# carcomputer_split3_top.net
KiCad netlist of a schematic drawn in EAGLE
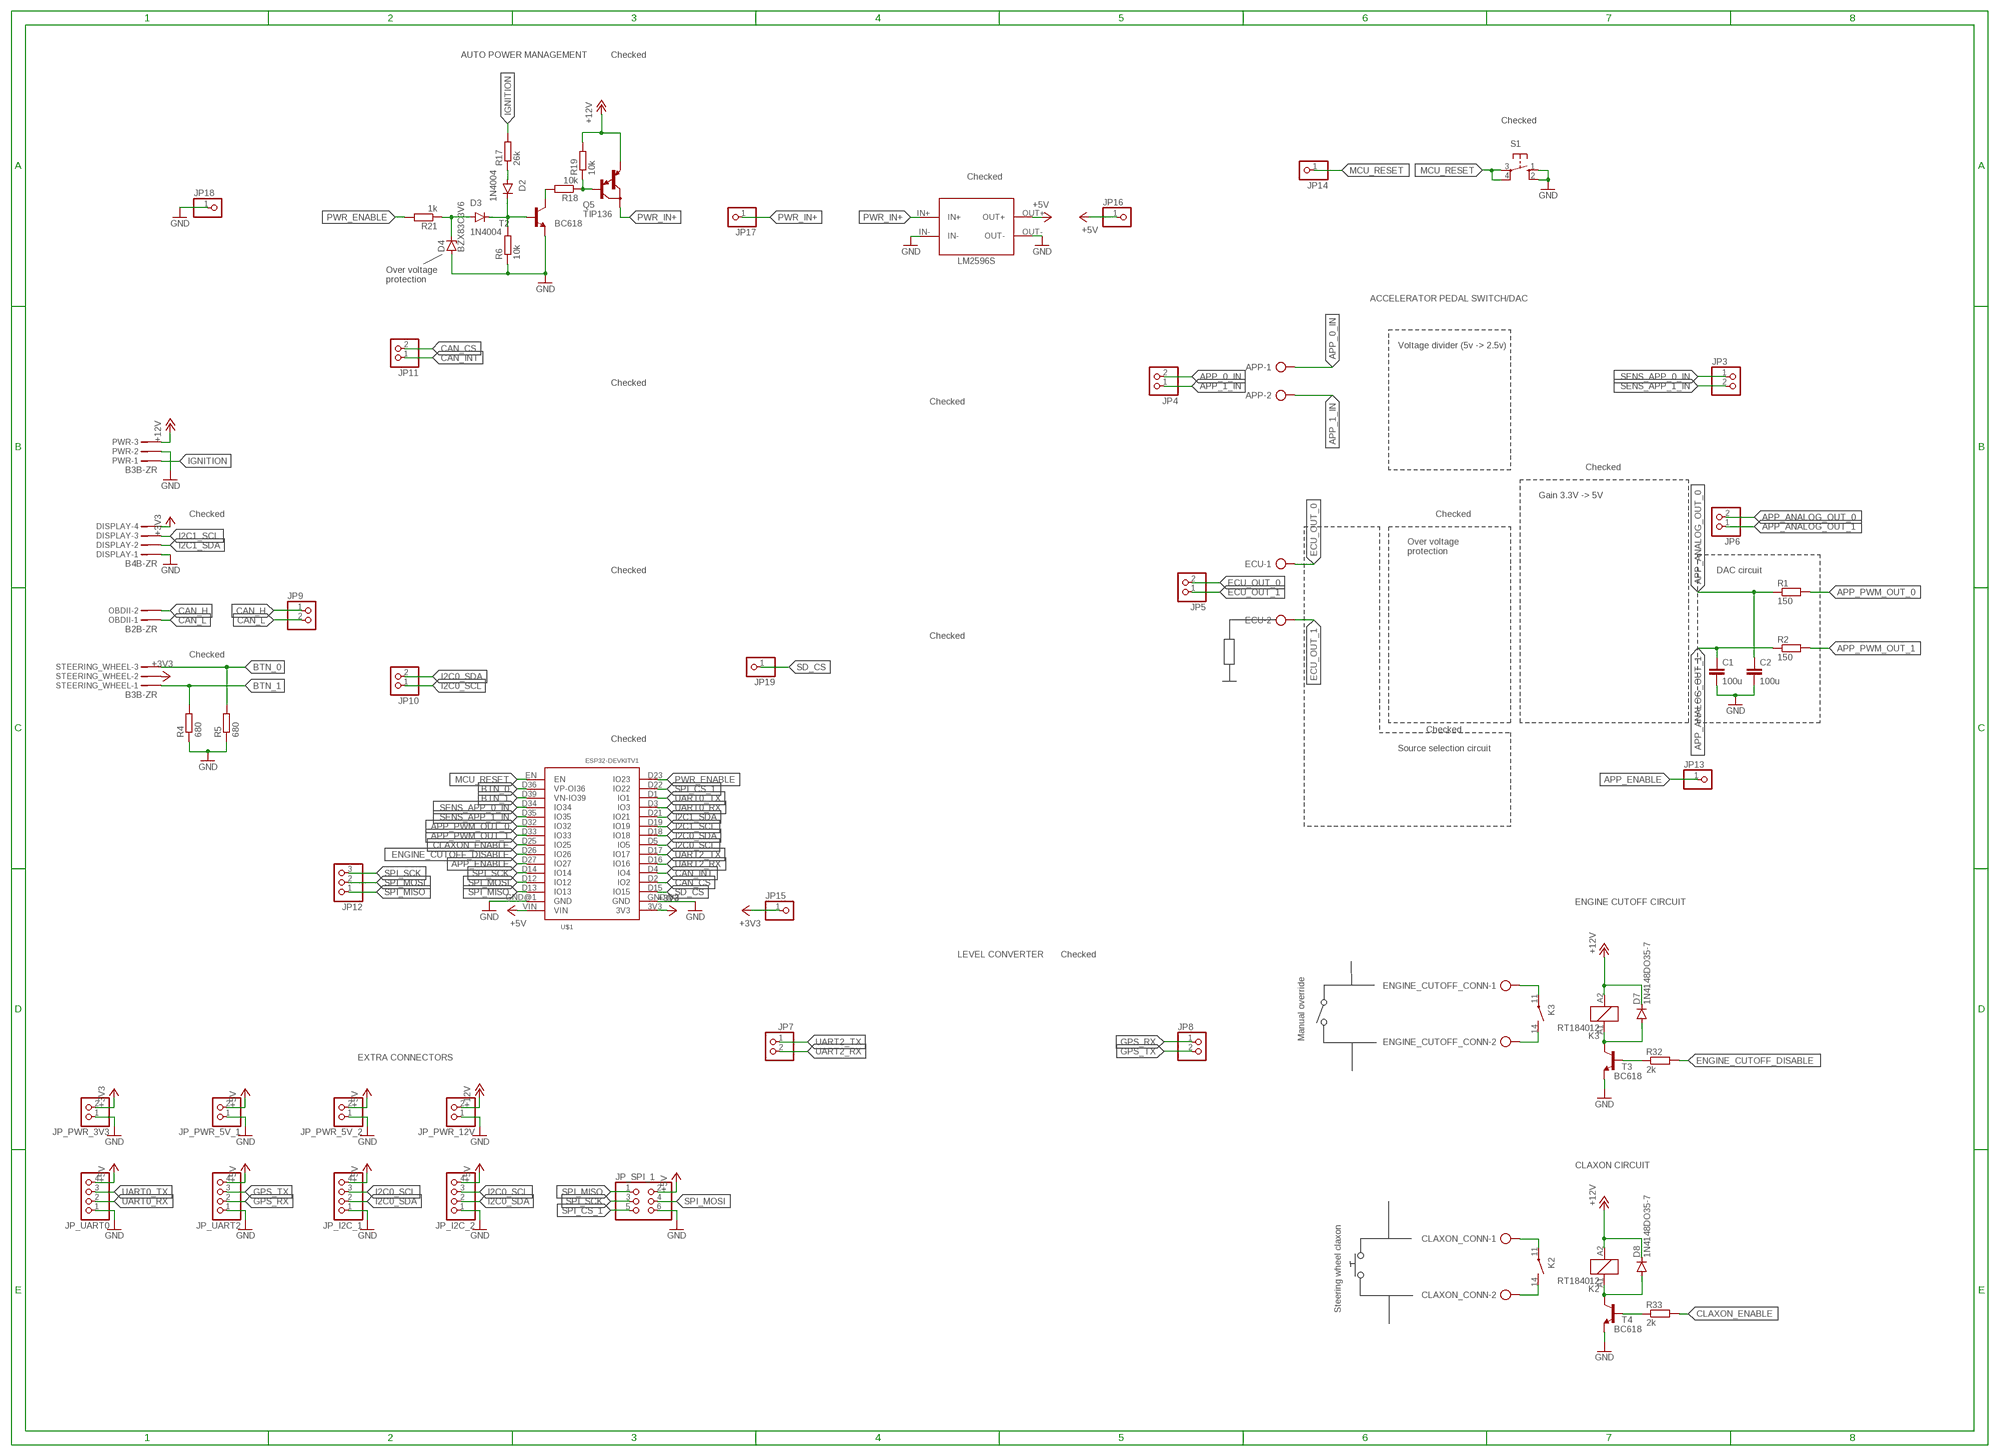
[diagram p0: schematic, sheet 1]

(export (version "E")
  (design (tool "Eeschema 10.0.6"))
  (components
    (comp (ref "APP")
      (value "AK300/2")
      (footprint "eagle-import:AK300_2")
      (libsource (lib "eagle-import") (part "AK300/2"))
    )
    (comp (ref "C1")
      (value "100u")
      (footprint "eagle-import:C025-050X050")
      (libsource (lib "eagle-import") (part "C-EU025-050X050"))
    )
    (comp (ref "C2")
      (value "100u")
      (footprint "eagle-import:C025-050X050")
      (libsource (lib "eagle-import") (part "C-EU025-050X050"))
    )
    (comp (ref "CLAXON_CONN")
      (value "AK300/2")
      (footprint "eagle-import:AK300_2")
      (libsource (lib "eagle-import") (part "AK300/2"))
    )
    (comp (ref "D2")
      (value "1N4004")
      (footprint "eagle-import:DO41-10")
      (libsource (lib "eagle-import") (part "1N4004"))
    )
    (comp (ref "D3")
      (value "1N4004")
      (footprint "eagle-import:DO41-10")
      (libsource (lib "eagle-import") (part "1N4004"))
    )
    (comp (ref "D4")
      (value "BZX83C3V6")
      (footprint "eagle-import:DO41Z10")
      (libsource (lib "eagle-import") (part "BZX85"))
    )
    (comp (ref "D7")
      (value "1N4148DO35-7")
      (footprint "eagle-import:DO35-7")
      (libsource (lib "eagle-import") (part "1N4148DO35-7"))
    )
    (comp (ref "D8")
      (value "1N4148DO35-7")
      (footprint "eagle-import:DO35-7")
      (libsource (lib "eagle-import") (part "1N4148DO35-7"))
    )
    (comp (ref "DISPLAY")
      (value "B4B-ZR")
      (footprint "eagle-import:B4B-ZR")
      (fields (field (name "MF") "FARNELL") (field (name "MPN") "B4B-ZR(LF)(SN)"))
      (libsource (lib "eagle-import") (part "?4B-ZRB"))
    )
    (comp (ref "ECU")
      (value "AK300/2")
      (footprint "eagle-import:AK300_2")
      (libsource (lib "eagle-import") (part "AK300/2"))
    )
    (comp (ref "ENGINE_CUTOFF_CONN")
      (value "AK300/2")
      (footprint "eagle-import:AK300_2")
      (libsource (lib "eagle-import") (part "AK300/2"))
    )
    (comp (ref "JP3")
      (value "PINHD-1X2")
      (footprint "eagle-import:1X02")
      (libsource (lib "eagle-import") (part "PINHD-1X2"))
    )
    (comp (ref "JP4")
      (value "PINHD-1X2")
      (footprint "eagle-import:1X02")
      (libsource (lib "eagle-import") (part "PINHD-1X2"))
    )
    (comp (ref "JP5")
      (value "PINHD-1X2")
      (footprint "eagle-import:1X02")
      (libsource (lib "eagle-import") (part "PINHD-1X2"))
    )
    (comp (ref "JP6")
      (value "PINHD-1X2")
      (footprint "eagle-import:1X02")
      (libsource (lib "eagle-import") (part "PINHD-1X2"))
    )
    (comp (ref "JP7")
      (value "PINHD-1X2")
      (footprint "eagle-import:1X02")
      (libsource (lib "eagle-import") (part "PINHD-1X2"))
    )
    (comp (ref "JP8")
      (value "PINHD-1X2")
      (footprint "eagle-import:1X02")
      (libsource (lib "eagle-import") (part "PINHD-1X2"))
    )
    (comp (ref "JP9")
      (value "PINHD-1X2")
      (footprint "eagle-import:1X02")
      (libsource (lib "eagle-import") (part "PINHD-1X2"))
    )
    (comp (ref "JP10")
      (value "PINHD-1X2")
      (footprint "eagle-import:1X02")
      (libsource (lib "eagle-import") (part "PINHD-1X2"))
    )
    (comp (ref "JP11")
      (value "PINHD-1X2")
      (footprint "eagle-import:1X02")
      (libsource (lib "eagle-import") (part "PINHD-1X2"))
    )
    (comp (ref "JP12")
      (value "PINHD-1X3")
      (footprint "eagle-import:1X03")
      (libsource (lib "eagle-import") (part "PINHD-1X3"))
    )
    (comp (ref "JP13")
      (value "PINHD-1X1")
      (footprint "eagle-import:1X01")
      (libsource (lib "eagle-import") (part "PINHD-1X1"))
    )
    (comp (ref "JP14")
      (value "PINHD-1X1")
      (footprint "eagle-import:1X01")
      (libsource (lib "eagle-import") (part "PINHD-1X1"))
    )
    (comp (ref "JP15")
      (value "PINHD-1X1")
      (footprint "eagle-import:1X01")
      (libsource (lib "eagle-import") (part "PINHD-1X1"))
    )
    (comp (ref "JP16")
      (value "PINHD-1X1")
      (footprint "eagle-import:1X01")
      (libsource (lib "eagle-import") (part "PINHD-1X1"))
    )
    (comp (ref "JP17")
      (value "PINHD-1X1")
      (footprint "eagle-import:1X01")
      (libsource (lib "eagle-import") (part "PINHD-1X1"))
    )
    (comp (ref "JP18")
      (value "PINHD-1X1")
      (footprint "eagle-import:1X01")
      (libsource (lib "eagle-import") (part "PINHD-1X1"))
    )
    (comp (ref "JP19")
      (value "PINHD-1X1")
      (footprint "eagle-import:1X01")
      (libsource (lib "eagle-import") (part "PINHD-1X1"))
    )
    (comp (ref "JP_I2C_1")
      (value "PINHD-1X4")
      (footprint "eagle-import:1X04")
      (libsource (lib "eagle-import") (part "PINHD-1X4"))
    )
    (comp (ref "JP_I2C_2")
      (value "PINHD-1X4")
      (footprint "eagle-import:1X04")
      (libsource (lib "eagle-import") (part "PINHD-1X4"))
    )
    (comp (ref "JP_PWR_3V3")
      (value "PINHD-1X2")
      (footprint "eagle-import:1X02")
      (libsource (lib "eagle-import") (part "PINHD-1X2"))
    )
    (comp (ref "JP_PWR_5V_1")
      (value "PINHD-1X2")
      (footprint "eagle-import:1X02")
      (libsource (lib "eagle-import") (part "PINHD-1X2"))
    )
    (comp (ref "JP_PWR_5V_2")
      (value "PINHD-1X2")
      (footprint "eagle-import:1X02")
      (libsource (lib "eagle-import") (part "PINHD-1X2"))
    )
    (comp (ref "JP_PWR_12V")
      (value "PINHD-1X2")
      (footprint "eagle-import:1X02")
      (libsource (lib "eagle-import") (part "PINHD-1X2"))
    )
    (comp (ref "JP_SPI_1")
      (value "PINHD-2X3")
      (footprint "eagle-import:2X03")
      (libsource (lib "eagle-import") (part "PINHD-2X3"))
    )
    (comp (ref "JP_UART0")
      (value "PINHD-1X4")
      (footprint "eagle-import:1X04")
      (libsource (lib "eagle-import") (part "PINHD-1X4"))
    )
    (comp (ref "JP_UART2")
      (value "PINHD-1X4")
      (footprint "eagle-import:1X04")
      (libsource (lib "eagle-import") (part "PINHD-1X4"))
    )
    (comp (ref "K2")
      (value "RT184012")
      (footprint "eagle-import:RT-N_O12A3.5")
      (fields (field (name "MF") "TYCO ELECTRONICS"))
      (libsource (lib "eagle-import") (part "RT?184012"))
    )
    (comp (ref "K3")
      (value "RT184012")
      (footprint "eagle-import:RT-N_O12A3.5")
      (fields (field (name "MF") "TYCO ELECTRONICS"))
      (libsource (lib "eagle-import") (part "RT?184012"))
    )
    (comp (ref "OBDII")
      (value "B2B-ZR")
      (footprint "eagle-import:B2B-ZR")
      (libsource (lib "eagle-import") (part "?2B-ZRB"))
    )
    (comp (ref "PWR")
      (value "B3B-ZR")
      (footprint "eagle-import:B3B-ZR")
      (libsource (lib "eagle-import") (part "?3B-ZRB"))
    )
    (comp (ref "Q5")
      (value "TIP136")
      (footprint "eagle-import:TO220")
      (libsource (lib "eagle-import") (part "TIP136"))
    )
    (comp (ref "R1")
      (value "150")
      (footprint "eagle-import:0207_7")
      (libsource (lib "eagle-import") (part "R-EU_0207/7"))
    )
    (comp (ref "R2")
      (value "150")
      (footprint "eagle-import:0207_7")
      (libsource (lib "eagle-import") (part "R-EU_0207/7"))
    )
    (comp (ref "R4")
      (value "680")
      (footprint "eagle-import:0207_7")
      (libsource (lib "eagle-import") (part "R-EU_0207/7"))
    )
    (comp (ref "R5")
      (value "680")
      (footprint "eagle-import:0207_7")
      (libsource (lib "eagle-import") (part "R-EU_0207/7"))
    )
    (comp (ref "R6")
      (value "10k")
      (footprint "eagle-import:0207_7")
      (libsource (lib "eagle-import") (part "R-EU_0207/7"))
    )
    (comp (ref "R17")
      (value "26k")
      (footprint "eagle-import:0207_7")
      (libsource (lib "eagle-import") (part "R-EU_0207/7"))
    )
    (comp (ref "R18")
      (value "10k")
      (footprint "eagle-import:0207_7")
      (libsource (lib "eagle-import") (part "R-EU_0207/7"))
    )
    (comp (ref "R19")
      (value "10k")
      (footprint "eagle-import:0207_7")
      (libsource (lib "eagle-import") (part "R-EU_0207/7"))
    )
    (comp (ref "R21")
      (value "1k")
      (footprint "eagle-import:0207_7")
      (libsource (lib "eagle-import") (part "R-EU_0207/7"))
    )
    (comp (ref "R32")
      (value "2k")
      (footprint "eagle-import:0207_7")
      (libsource (lib "eagle-import") (part "R-EU_0207/7"))
    )
    (comp (ref "R33")
      (value "2k")
      (footprint "eagle-import:0207_7")
      (libsource (lib "eagle-import") (part "R-EU_0207/7"))
    )
    (comp (ref "S1")
      (value "10-XX")
      (footprint "eagle-import:B3F-10XX")
      (fields (field (name "MPN") "B3F-1000"))
      (libsource (lib "eagle-import") (part "10-XX"))
    )
    (comp (ref "STEERING_WHEEL")
      (value "B3B-ZR")
      (footprint "eagle-import:B3B-ZR")
      (libsource (lib "eagle-import") (part "?3B-ZRB"))
    )
    (comp (ref "T2")
      (value "BC618")
      (footprint "eagle-import:TO92-EBC")
      (libsource (lib "eagle-import") (part "BC618"))
    )
    (comp (ref "T3")
      (value "BC618")
      (footprint "eagle-import:TO92-EBC")
      (libsource (lib "eagle-import") (part "BC618"))
    )
    (comp (ref "T4")
      (value "BC618")
      (footprint "eagle-import:TO92-EBC")
      (libsource (lib "eagle-import") (part "BC618"))
    )
    (comp (ref "U$1")
      (value "ESP32DEVKITV1")
      (footprint "eagle-import:ESP32-DEVKITV1")
      (libsource (lib "eagle-import") (part "ESP32DEVKITV1"))
    )
    (comp (ref "U$4")
      (value "LM2596S")
      (footprint "eagle-import:LM2596S")
      (libsource (lib "eagle-import") (part "LM2596S"))
    )
  )
  (nets
    (net (code "1") (name "+3V3") (class "Default")
      (node (ref "DISPLAY") (pin "4") (pinfunction "1_4") (pintype "passive"))
      (node (ref "JP15") (pin "1") (pinfunction "1_1") (pintype "passive"))
      (node (ref "JP_PWR_3V3") (pin "2") (pinfunction "2_2") (pintype "passive"))
      (node (ref "STEERING_WHEEL") (pin "2") (pinfunction "1_2") (pintype "passive"))
      (node (ref "U$1") (pin "3V3") (pinfunction "3V3_3V3") (pintype "bidirectional"))
    )
    (net (code "2") (name "+5V") (class "Default")
      (node (ref "JP16") (pin "1") (pinfunction "1_1") (pintype "passive"))
      (node (ref "JP_I2C_1") (pin "4") (pinfunction "4_4") (pintype "passive"))
      (node (ref "JP_I2C_2") (pin "4") (pinfunction "4_4") (pintype "passive"))
      (node (ref "JP_PWR_5V_1") (pin "2") (pinfunction "2_2") (pintype "passive"))
      (node (ref "JP_PWR_5V_2") (pin "2") (pinfunction "2_2") (pintype "passive"))
      (node (ref "JP_SPI_1") (pin "2") (pinfunction "2_2") (pintype "passive"))
      (node (ref "JP_UART0") (pin "4") (pinfunction "4_4") (pintype "passive"))
      (node (ref "JP_UART2") (pin "4") (pinfunction "4_4") (pintype "passive"))
      (node (ref "U$1") (pin "VIN") (pinfunction "VIN_VIN") (pintype "bidirectional"))
      (node (ref "U$4") (pin "OUT+") (pinfunction "OUT+_OUT+") (pintype "bidirectional"))
    )
    (net (code "3") (name "+12V") (class "Default")
      (node (ref "D7") (pin "C") (pinfunction "C_C") (pintype "passive"))
      (node (ref "D8") (pin "C") (pinfunction "C_C") (pintype "passive"))
      (node (ref "JP_PWR_12V") (pin "2") (pinfunction "2_2") (pintype "passive"))
      (node (ref "K2") (pin "A2") (pinfunction "2_A2") (pintype "passive"))
      (node (ref "K3") (pin "A2") (pinfunction "2_A2") (pintype "passive"))
      (node (ref "PWR") (pin "3") (pinfunction "1_3") (pintype "passive"))
      (node (ref "Q5") (pin "3") (pinfunction "E_3") (pintype "passive"))
      (node (ref "R19") (pin "2") (pinfunction "2_2") (pintype "passive"))
    )
    (net (code "4") (name "APP_0_IN") (class "Default")
      (node (ref "APP") (pin "1") (pinfunction "KL_1") (pintype "passive"))
      (node (ref "JP4") (pin "2") (pinfunction "2_2") (pintype "passive"))
    )
    (net (code "5") (name "APP_1_IN") (class "Default")
      (node (ref "APP") (pin "2") (pinfunction "KL_2") (pintype "passive"))
      (node (ref "JP4") (pin "1") (pinfunction "1_1") (pintype "passive"))
    )
    (net (code "6") (name "APP_ANALOG_OUT_0") (class "Default")
      (node (ref "C2") (pin "1") (pinfunction "1_1") (pintype "passive"))
      (node (ref "JP6") (pin "2") (pinfunction "2_2") (pintype "passive"))
      (node (ref "R1") (pin "1") (pinfunction "1_1") (pintype "passive"))
    )
    (net (code "7") (name "APP_ANALOG_OUT_1") (class "Default")
      (node (ref "C1") (pin "1") (pinfunction "1_1") (pintype "passive"))
      (node (ref "JP6") (pin "1") (pinfunction "1_1") (pintype "passive"))
      (node (ref "R2") (pin "1") (pinfunction "1_1") (pintype "passive"))
    )
    (net (code "8") (name "APP_ENABLE") (class "Default")
      (node (ref "JP13") (pin "1") (pinfunction "1_1") (pintype "passive"))
      (node (ref "U$1") (pin "D27") (pinfunction "IO27_D27") (pintype "bidirectional"))
    )
    (net (code "9") (name "APP_PWM_OUT_0") (class "Default")
      (node (ref "R1") (pin "2") (pinfunction "2_2") (pintype "passive"))
      (node (ref "U$1") (pin "D32") (pinfunction "IO32_D32") (pintype "bidirectional"))
    )
    (net (code "10") (name "APP_PWM_OUT_1") (class "Default")
      (node (ref "R2") (pin "2") (pinfunction "2_2") (pintype "passive"))
      (node (ref "U$1") (pin "D33") (pinfunction "IO33_D33") (pintype "bidirectional"))
    )
    (net (code "11") (name "BTN_0") (class "Default")
      (node (ref "R5") (pin "2") (pinfunction "2_2") (pintype "passive"))
      (node (ref "STEERING_WHEEL") (pin "3") (pinfunction "1_3") (pintype "passive"))
      (node (ref "U$1") (pin "D36") (pinfunction "VP-OI36_D36") (pintype "bidirectional"))
    )
    (net (code "12") (name "BTN_1") (class "Default")
      (node (ref "R4") (pin "2") (pinfunction "2_2") (pintype "passive"))
      (node (ref "STEERING_WHEEL") (pin "1") (pinfunction "1_1") (pintype "passive"))
      (node (ref "U$1") (pin "D39") (pinfunction "VN-IO39_D39") (pintype "bidirectional"))
    )
    (net (code "13") (name "CAN_CS") (class "Default")
      (node (ref "JP11") (pin "2") (pinfunction "2_2") (pintype "passive"))
      (node (ref "U$1") (pin "D2") (pinfunction "IO2_D2") (pintype "bidirectional"))
    )
    (net (code "14") (name "CAN_H") (class "Default")
      (node (ref "JP9") (pin "1") (pinfunction "1_1") (pintype "passive"))
      (node (ref "OBDII") (pin "2") (pinfunction "1_2") (pintype "passive"))
    )
    (net (code "15") (name "CAN_INT") (class "Default")
      (node (ref "JP11") (pin "1") (pinfunction "1_1") (pintype "passive"))
      (node (ref "U$1") (pin "D4") (pinfunction "IO4_D4") (pintype "bidirectional"))
    )
    (net (code "16") (name "CAN_L") (class "Default")
      (node (ref "JP9") (pin "2") (pinfunction "2_2") (pintype "passive"))
      (node (ref "OBDII") (pin "1") (pinfunction "1_1") (pintype "passive"))
    )
    (net (code "17") (name "CLAXON_ENABLE") (class "Default")
      (node (ref "R33") (pin "2") (pinfunction "2_2") (pintype "passive"))
      (node (ref "U$1") (pin "D25") (pinfunction "IO25_D25") (pintype "bidirectional"))
    )
    (net (code "18") (name "ECU_OUT_0") (class "Default")
      (node (ref "ECU") (pin "1") (pinfunction "KL_1") (pintype "passive"))
      (node (ref "JP5") (pin "2") (pinfunction "2_2") (pintype "passive"))
    )
    (net (code "19") (name "ECU_OUT_1") (class "Default")
      (node (ref "ECU") (pin "2") (pinfunction "KL_2") (pintype "passive"))
      (node (ref "JP5") (pin "1") (pinfunction "1_1") (pintype "passive"))
    )
    (net (code "20") (name "ENGINE_CUTOFF_DISABLE") (class "Default")
      (node (ref "R32") (pin "2") (pinfunction "2_2") (pintype "passive"))
      (node (ref "U$1") (pin "D26") (pinfunction "IO26_D26") (pintype "bidirectional"))
    )
    (net (code "21") (name "GND") (class "Default")
      (node (ref "C1") (pin "2") (pinfunction "2_2") (pintype "passive"))
      (node (ref "C2") (pin "2") (pinfunction "2_2") (pintype "passive"))
      (node (ref "D4") (pin "A") (pinfunction "A_A") (pintype "passive"))
      (node (ref "DISPLAY") (pin "1") (pinfunction "1_1") (pintype "passive"))
      (node (ref "JP18") (pin "1") (pinfunction "1_1") (pintype "passive"))
      (node (ref "JP_I2C_1") (pin "1") (pinfunction "1_1") (pintype "passive"))
      (node (ref "JP_I2C_2") (pin "1") (pinfunction "1_1") (pintype "passive"))
      (node (ref "JP_PWR_12V") (pin "1") (pinfunction "1_1") (pintype "passive"))
      (node (ref "JP_PWR_3V3") (pin "1") (pinfunction "1_1") (pintype "passive"))
      (node (ref "JP_PWR_5V_1") (pin "1") (pinfunction "1_1") (pintype "passive"))
      (node (ref "JP_PWR_5V_2") (pin "1") (pinfunction "1_1") (pintype "passive"))
      (node (ref "JP_SPI_1") (pin "6") (pinfunction "6_6") (pintype "passive"))
      (node (ref "JP_UART0") (pin "1") (pinfunction "1_1") (pintype "passive"))
      (node (ref "JP_UART2") (pin "1") (pinfunction "1_1") (pintype "passive"))
      (node (ref "PWR") (pin "2") (pinfunction "1_2") (pintype "passive"))
      (node (ref "R4") (pin "1") (pinfunction "1_1") (pintype "passive"))
      (node (ref "R5") (pin "1") (pinfunction "1_1") (pintype "passive"))
      (node (ref "R6") (pin "1") (pinfunction "1_1") (pintype "passive"))
      (node (ref "S1") (pin "1") (pinfunction "S_1") (pintype "passive"))
      (node (ref "S1") (pin "2") (pinfunction "S1_2") (pintype "passive"))
      (node (ref "T2") (pin "E") (pinfunction "E_E") (pintype "passive"))
      (node (ref "T3") (pin "E") (pinfunction "E_E") (pintype "passive"))
      (node (ref "T4") (pin "E") (pinfunction "E_E") (pintype "passive"))
      (node (ref "U$1") (pin "GND@1") (pinfunction "GND_GND@1") (pintype "bidirectional"))
      (node (ref "U$1") (pin "GND@2") (pinfunction "GND_GND@2") (pintype "bidirectional"))
      (node (ref "U$4") (pin "IN-") (pinfunction "IN-_IN-") (pintype "bidirectional"))
      (node (ref "U$4") (pin "OUT-") (pinfunction "OUT-_OUT-") (pintype "bidirectional"))
    )
    (net (code "22") (name "GPS_RX") (class "Default")
      (node (ref "JP8") (pin "1") (pinfunction "1_1") (pintype "passive"))
      (node (ref "JP_UART2") (pin "2") (pinfunction "2_2") (pintype "passive"))
    )
    (net (code "23") (name "GPS_TX") (class "Default")
      (node (ref "JP8") (pin "2") (pinfunction "2_2") (pintype "passive"))
      (node (ref "JP_UART2") (pin "3") (pinfunction "3_3") (pintype "passive"))
    )
    (net (code "24") (name "I2C0_SCL") (class "Default")
      (node (ref "JP10") (pin "1") (pinfunction "1_1") (pintype "passive"))
      (node (ref "JP_I2C_1") (pin "3") (pinfunction "3_3") (pintype "passive"))
      (node (ref "JP_I2C_2") (pin "3") (pinfunction "3_3") (pintype "passive"))
      (node (ref "U$1") (pin "D5") (pinfunction "IO5_D5") (pintype "bidirectional"))
    )
    (net (code "25") (name "I2C0_SDA") (class "Default")
      (node (ref "JP10") (pin "2") (pinfunction "2_2") (pintype "passive"))
      (node (ref "JP_I2C_1") (pin "2") (pinfunction "2_2") (pintype "passive"))
      (node (ref "JP_I2C_2") (pin "2") (pinfunction "2_2") (pintype "passive"))
      (node (ref "U$1") (pin "D18") (pinfunction "IO18_D18") (pintype "bidirectional"))
    )
    (net (code "26") (name "I2C1_SCL") (class "Default")
      (node (ref "DISPLAY") (pin "3") (pinfunction "1_3") (pintype "passive"))
      (node (ref "U$1") (pin "D19") (pinfunction "IO19_D19") (pintype "bidirectional"))
    )
    (net (code "27") (name "I2C1_SDA") (class "Default")
      (node (ref "DISPLAY") (pin "2") (pinfunction "1_2") (pintype "passive"))
      (node (ref "U$1") (pin "D21") (pinfunction "IO21_D21") (pintype "bidirectional"))
    )
    (net (code "28") (name "IGNITION") (class "Default")
      (node (ref "PWR") (pin "1") (pinfunction "1_1") (pintype "passive"))
      (node (ref "R17") (pin "2") (pinfunction "2_2") (pintype "passive"))
    )
    (net (code "29") (name "MCU_RESET") (class "Default")
      (node (ref "JP14") (pin "1") (pinfunction "1_1") (pintype "passive"))
      (node (ref "S1") (pin "3") (pinfunction "P_3") (pintype "passive"))
      (node (ref "S1") (pin "4") (pinfunction "P1_4") (pintype "passive"))
      (node (ref "U$1") (pin "EN") (pinfunction "EN_EN") (pintype "bidirectional"))
    )
    (net (code "30") (name "Net-(CLAXON_CONNA-KL)") (class "Default")
      (node (ref "CLAXON_CONN") (pin "1") (pinfunction "KL_1") (pintype "passive"))
      (node (ref "K2") (pin "11") (pinfunction "P_11") (pintype "passive"))
    )
    (net (code "31") (name "Net-(CLAXON_CONNB-KL)") (class "Default")
      (node (ref "CLAXON_CONN") (pin "2") (pinfunction "KL_2") (pintype "passive"))
      (node (ref "K2") (pin "14") (pinfunction "S_14") (pintype "passive"))
    )
    (net (code "32") (name "Net-(D2-PadA)") (class "Default")
      (node (ref "D2") (pin "A") (pinfunction "A_A") (pintype "passive"))
      (node (ref "R17") (pin "1") (pinfunction "1_1") (pintype "passive"))
    )
    (net (code "33") (name "Net-(D2-PadC)") (class "Default")
      (node (ref "D2") (pin "C") (pinfunction "C_C") (pintype "passive"))
      (node (ref "D3") (pin "C") (pinfunction "C_C") (pintype "passive"))
      (node (ref "R6") (pin "2") (pinfunction "2_2") (pintype "passive"))
      (node (ref "T2") (pin "B") (pinfunction "B_B") (pintype "passive"))
    )
    (net (code "34") (name "Net-(D3-PadA)") (class "Default")
      (node (ref "D3") (pin "A") (pinfunction "A_A") (pintype "passive"))
      (node (ref "D4") (pin "C") (pinfunction "C_C") (pintype "passive"))
      (node (ref "R21") (pin "1") (pinfunction "1_1") (pintype "passive"))
    )
    (net (code "35") (name "Net-(ENGINE_CUTOFF_CONNA-KL)") (class "Default")
      (node (ref "ENGINE_CUTOFF_CONN") (pin "1") (pinfunction "KL_1") (pintype "passive"))
      (node (ref "K3") (pin "11") (pinfunction "P_11") (pintype "passive"))
    )
    (net (code "36") (name "Net-(ENGINE_CUTOFF_CONNB-KL)") (class "Default")
      (node (ref "ENGINE_CUTOFF_CONN") (pin "2") (pinfunction "KL_2") (pintype "passive"))
      (node (ref "K3") (pin "14") (pinfunction "S_14") (pintype "passive"))
    )
    (net (code "37") (name "Net-(K2A-1)") (class "Default")
      (node (ref "D8") (pin "A") (pinfunction "A_A") (pintype "passive"))
      (node (ref "K2") (pin "A1") (pinfunction "1_A1") (pintype "passive"))
      (node (ref "T4") (pin "C") (pinfunction "C_C") (pintype "passive"))
    )
    (net (code "38") (name "Net-(K3A-1)") (class "Default")
      (node (ref "D7") (pin "A") (pinfunction "A_A") (pintype "passive"))
      (node (ref "K3") (pin "A1") (pinfunction "1_A1") (pintype "passive"))
      (node (ref "T3") (pin "C") (pinfunction "C_C") (pintype "passive"))
    )
    (net (code "39") (name "Net-(Q5-B)") (class "Default")
      (node (ref "Q5") (pin "1") (pinfunction "B_1") (pintype "passive"))
      (node (ref "R18") (pin "1") (pinfunction "1_1") (pintype "passive"))
      (node (ref "R19") (pin "1") (pinfunction "1_1") (pintype "passive"))
    )
    (net (code "40") (name "Net-(R18-Pad2)") (class "Default")
      (node (ref "R18") (pin "2") (pinfunction "2_2") (pintype "passive"))
      (node (ref "T2") (pin "C") (pinfunction "C_C") (pintype "passive"))
    )
    (net (code "41") (name "Net-(R32-Pad1)") (class "Default")
      (node (ref "R32") (pin "1") (pinfunction "1_1") (pintype "passive"))
      (node (ref "T3") (pin "B") (pinfunction "B_B") (pintype "passive"))
    )
    (net (code "42") (name "Net-(R33-Pad1)") (class "Default")
      (node (ref "R33") (pin "1") (pinfunction "1_1") (pintype "passive"))
      (node (ref "T4") (pin "B") (pinfunction "B_B") (pintype "passive"))
    )
    (net (code "43") (name "PWR_ENABLE") (class "Default")
      (node (ref "R21") (pin "2") (pinfunction "2_2") (pintype "passive"))
      (node (ref "U$1") (pin "D23") (pinfunction "IO23_D23") (pintype "bidirectional"))
    )
    (net (code "44") (name "PWR_IN+") (class "Default")
      (node (ref "JP17") (pin "1") (pinfunction "1_1") (pintype "passive"))
      (node (ref "Q5") (pin "2") (pinfunction "C_2") (pintype "passive"))
      (node (ref "U$4") (pin "IN+") (pinfunction "IN+_IN+") (pintype "bidirectional"))
    )
    (net (code "45") (name "SD_CS") (class "Default")
      (node (ref "JP19") (pin "1") (pinfunction "1_1") (pintype "passive"))
      (node (ref "U$1") (pin "D15") (pinfunction "IO15_D15") (pintype "bidirectional"))
    )
    (net (code "46") (name "SENS_APP_0_IN") (class "Default")
      (node (ref "JP3") (pin "1") (pinfunction "1_1") (pintype "passive"))
      (node (ref "U$1") (pin "D34") (pinfunction "IO34_D34") (pintype "bidirectional"))
    )
    (net (code "47") (name "SENS_APP_1_IN") (class "Default")
      (node (ref "JP3") (pin "2") (pinfunction "2_2") (pintype "passive"))
      (node (ref "U$1") (pin "D35") (pinfunction "IO35_D35") (pintype "bidirectional"))
    )
    (net (code "48") (name "SPI_CS_1") (class "Default")
      (node (ref "JP_SPI_1") (pin "5") (pinfunction "5_5") (pintype "passive"))
      (node (ref "U$1") (pin "D22") (pinfunction "IO22_D22") (pintype "bidirectional"))
    )
    (net (code "49") (name "SPI_MISO") (class "Default")
      (node (ref "JP12") (pin "1") (pinfunction "1_1") (pintype "passive"))
      (node (ref "JP_SPI_1") (pin "1") (pinfunction "1_1") (pintype "passive"))
      (node (ref "U$1") (pin "D13") (pinfunction "IO13_D13") (pintype "bidirectional"))
    )
    (net (code "50") (name "SPI_MOSI") (class "Default")
      (node (ref "JP12") (pin "2") (pinfunction "2_2") (pintype "passive"))
      (node (ref "JP_SPI_1") (pin "4") (pinfunction "4_4") (pintype "passive"))
      (node (ref "U$1") (pin "D12") (pinfunction "IO12_D12") (pintype "bidirectional"))
    )
    (net (code "51") (name "SPI_SCK") (class "Default")
      (node (ref "JP12") (pin "3") (pinfunction "3_3") (pintype "passive"))
      (node (ref "JP_SPI_1") (pin "3") (pinfunction "3_3") (pintype "passive"))
      (node (ref "U$1") (pin "D14") (pinfunction "IO14_D14") (pintype "bidirectional"))
    )
    (net (code "52") (name "UART0_RX") (class "Default")
      (node (ref "JP_UART0") (pin "2") (pinfunction "2_2") (pintype "passive"))
      (node (ref "U$1") (pin "D3") (pinfunction "IO3_D3") (pintype "bidirectional"))
    )
    (net (code "53") (name "UART0_TX") (class "Default")
      (node (ref "JP_UART0") (pin "3") (pinfunction "3_3") (pintype "passive"))
      (node (ref "U$1") (pin "D1") (pinfunction "IO1_D1") (pintype "bidirectional"))
    )
    (net (code "54") (name "UART2_RX") (class "Default")
      (node (ref "JP7") (pin "2") (pinfunction "2_2") (pintype "passive"))
      (node (ref "U$1") (pin "D16") (pinfunction "IO16_D16") (pintype "bidirectional"))
    )
    (net (code "55") (name "UART2_TX") (class "Default")
      (node (ref "JP7") (pin "1") (pinfunction "1_1") (pintype "passive"))
      (node (ref "U$1") (pin "D17") (pinfunction "IO17_D17") (pintype "bidirectional"))
    )
  )
)
